# PowerSupply.net
KiCad netlist of a schematic drawn in Altium Designer
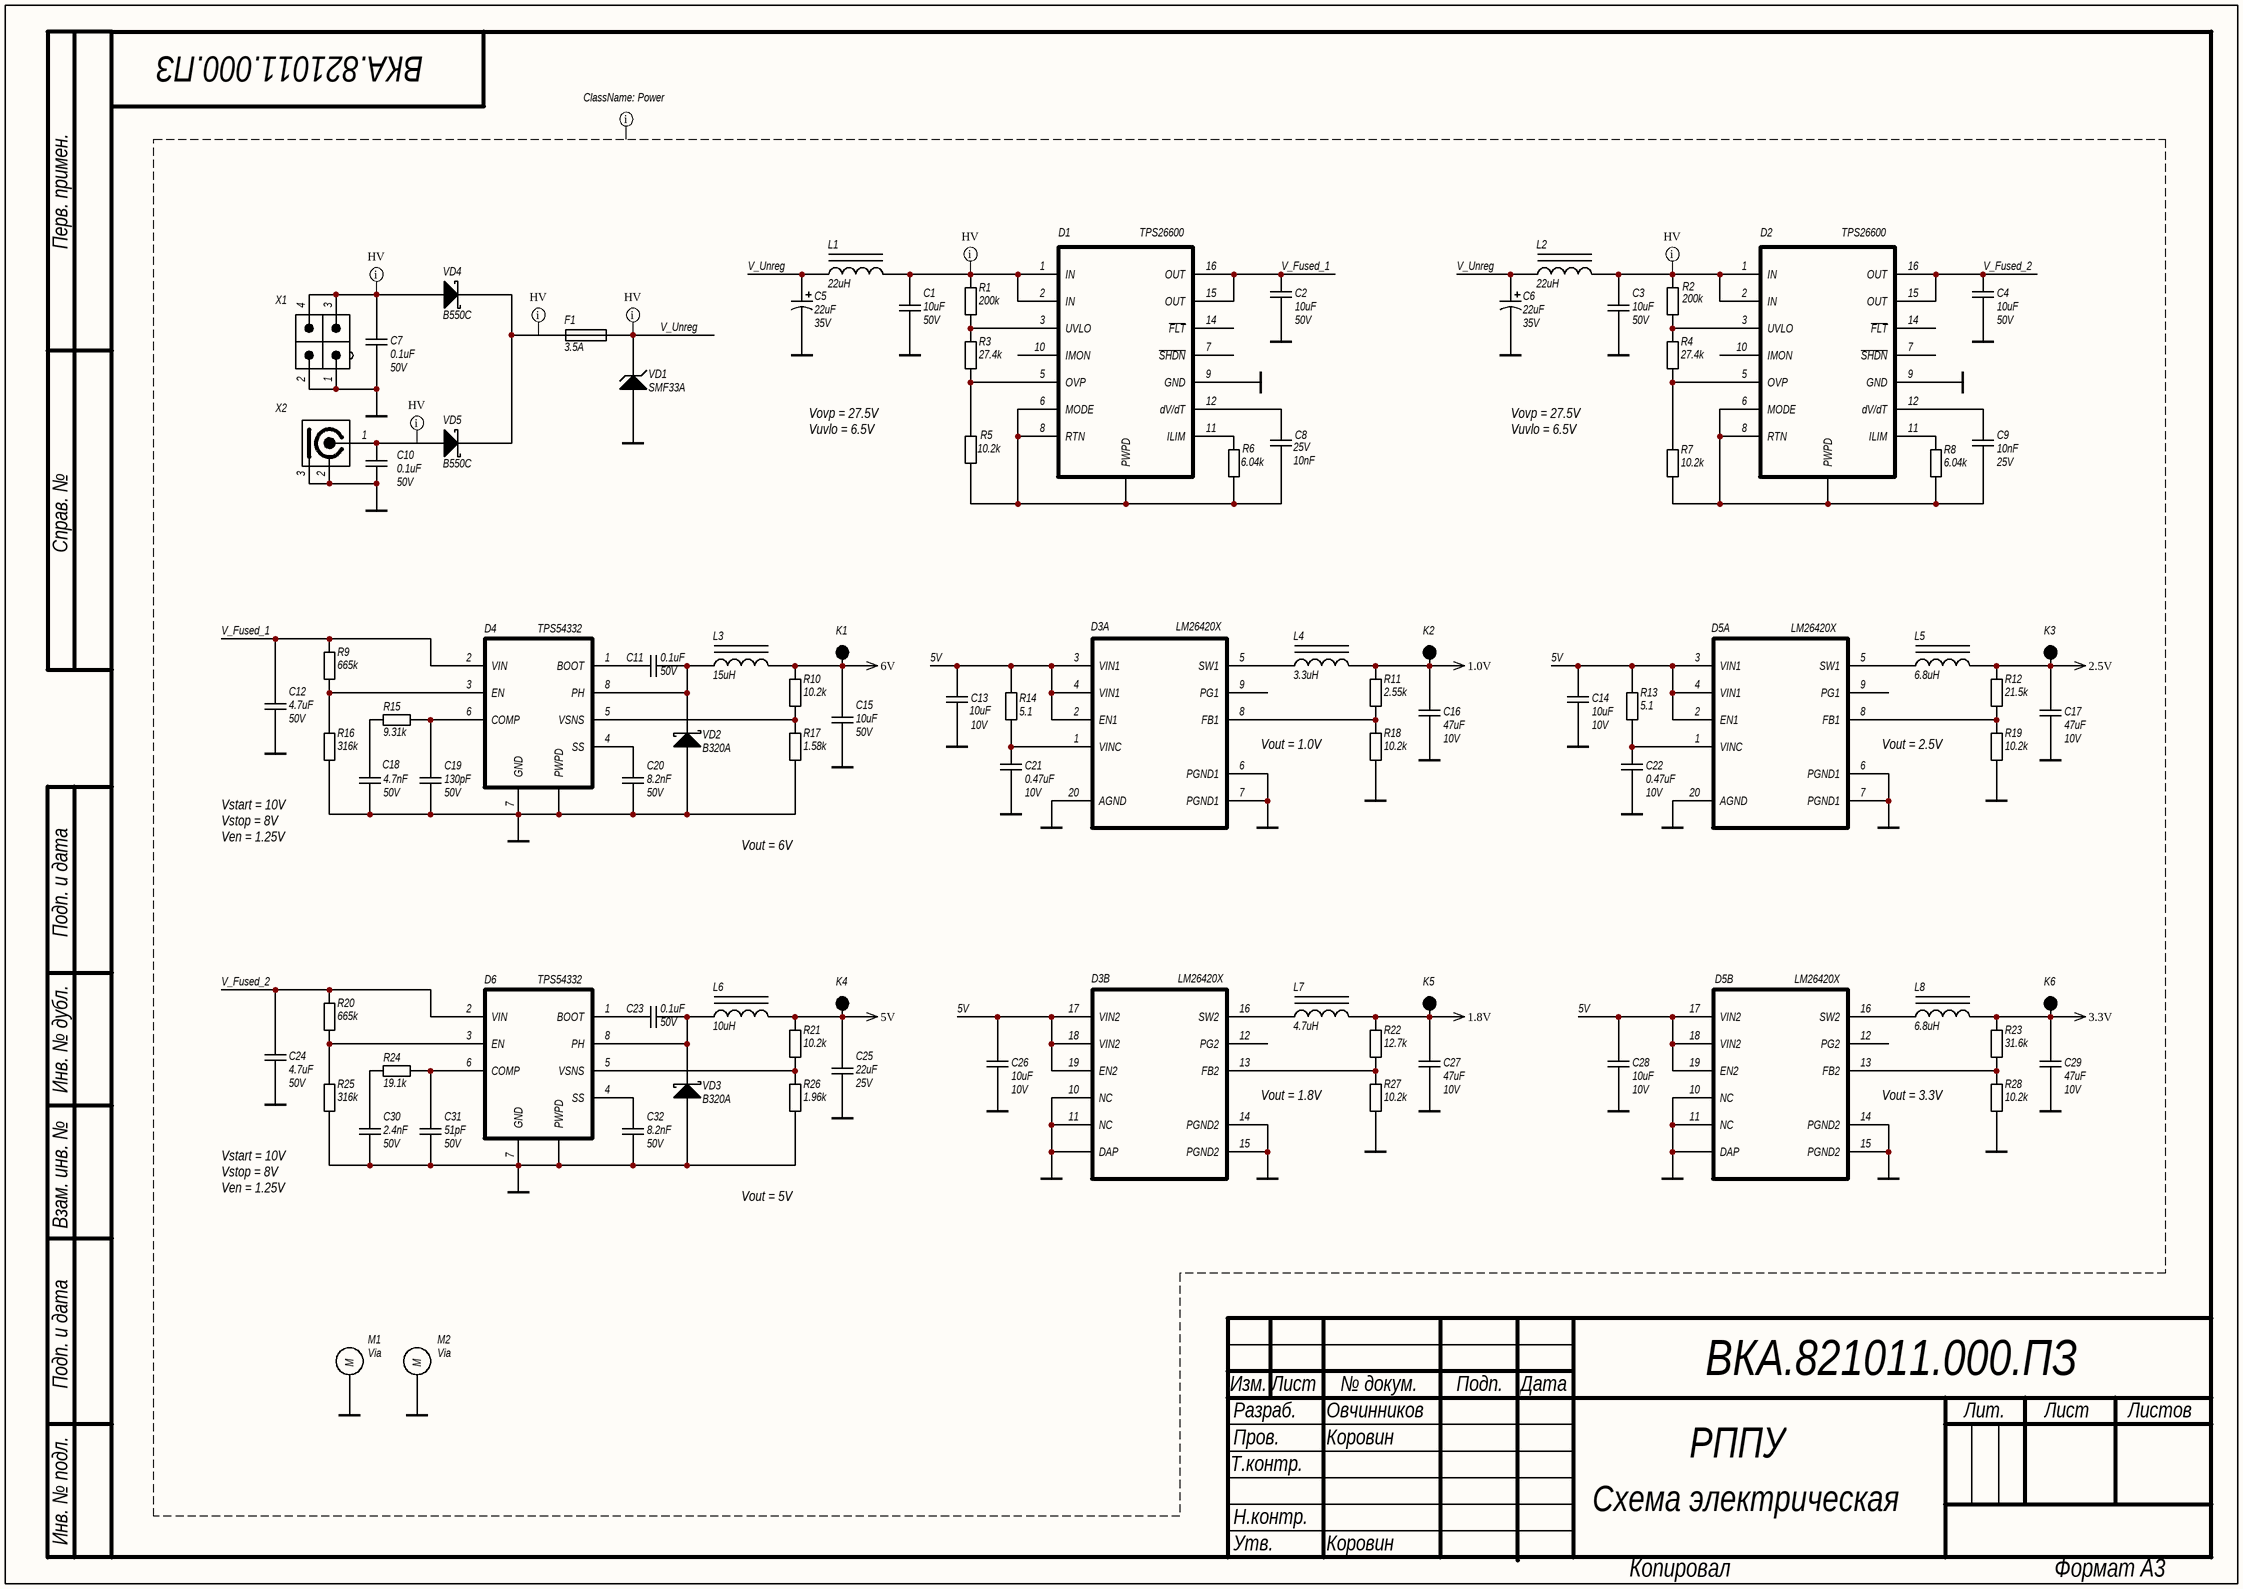
[diagram p0: PowerSupply.SchDoc]

(export (version "E")
  (design (tool "Eeschema 10.0.6"))
  (components
    (comp (ref "C1")
      (value "10uF")
      (footprint "C1210")
      (description "SMD Capacitor")
      (fields
        (field (name "MANUFACTURER") "Murata")
        (field (name "TOLERANCE") "10%")
        (field (name "VOLTAGE") "50V")
      )
      (libsource (lib "Kintex_SDR") (part "CAP uF"))
    )
    (comp (ref "C2")
      (value "10uF")
      (footprint "C1210")
      (description "SMD Capacitor")
      (fields
        (field (name "MANUFACTURER") "Murata")
        (field (name "TOLERANCE") "10%")
        (field (name "VOLTAGE") "50V")
      )
      (libsource (lib "Kintex_SDR") (part "CAP uF"))
    )
    (comp (ref "C3")
      (value "10uF")
      (footprint "C1210")
      (description "SMD Capacitor")
      (fields
        (field (name "MANUFACTURER") "Murata")
        (field (name "TOLERANCE") "10%")
        (field (name "VOLTAGE") "50V")
      )
      (libsource (lib "Kintex_SDR") (part "CAP uF"))
    )
    (comp (ref "C4")
      (value "10uF")
      (footprint "C1210")
      (description "SMD Capacitor")
      (fields
        (field (name "MANUFACTURER") "Murata")
        (field (name "TOLERANCE") "10%")
        (field (name "VOLTAGE") "50V")
      )
      (libsource (lib "Kintex_SDR") (part "CAP uF"))
    )
    (comp (ref "C5")
      (value "22uF")
      (footprint "Tantalum_D")
      (description "Tantalum Polarity SMD Capacitor")
      (fields
        (field (name "MANUFACTURER") "AVX Corporation")
        (field (name "TOLERANCE") "10%")
        (field (name "VOLTAGE") "35V")
      )
      (libsource (lib "Kintex_SDR") (part "Cap Polarity"))
    )
    (comp (ref "C6")
      (value "22uF")
      (footprint "Tantalum_D")
      (description "Tantalum Polarity SMD Capacitor")
      (fields
        (field (name "MANUFACTURER") "AVX Corporation")
        (field (name "TOLERANCE") "10%")
        (field (name "VOLTAGE") "35V")
      )
      (libsource (lib "Kintex_SDR") (part "Cap Polarity"))
    )
    (comp (ref "C7")
      (value "0.1uF")
      (footprint "C0402")
      (description "SMD Capacitor")
      (fields
        (field (name "MANUFACTURER") "Murata")
        (field (name "TOLERANCE") "10%")
        (field (name "VOLTAGE") "50V")
      )
      (libsource (lib "Kintex_SDR") (part "CAP"))
    )
    (comp (ref "C8")
      (value "10nF")
      (footprint "C0402")
      (description "SMD Capacitor")
      (fields
        (field (name "MANUFACTURER") "Murata")
        (field (name "TOLERANCE") "5%")
        (field (name "VOLTAGE") "25V")
      )
      (libsource (lib "Kintex_SDR") (part "CAP"))
    )
    (comp (ref "C9")
      (value "10nF")
      (footprint "C0402")
      (description "SMD Capacitor")
      (fields
        (field (name "MANUFACTURER") "Murata")
        (field (name "TOLERANCE") "5%")
        (field (name "VOLTAGE") "25V")
      )
      (libsource (lib "Kintex_SDR") (part "CAP"))
    )
    (comp (ref "C10")
      (value "0.1uF")
      (footprint "C0402")
      (description "SMD Capacitor")
      (fields
        (field (name "MANUFACTURER") "Murata")
        (field (name "TOLERANCE") "10%")
        (field (name "VOLTAGE") "50V")
      )
      (libsource (lib "Kintex_SDR") (part "CAP"))
    )
    (comp (ref "C11")
      (value "0.1uF")
      (footprint "C0402")
      (description "SMD Capacitor")
      (fields
        (field (name "MANUFACTURER") "Murata")
        (field (name "TOLERANCE") "10%")
        (field (name "VOLTAGE") "50V")
      )
      (libsource (lib "Kintex_SDR") (part "CAP"))
    )
    (comp (ref "C12")
      (value "4.7uF")
      (footprint "C0805")
      (description "SMD Capacitor")
      (fields
        (field (name "MANUFACTURER") "Murata")
        (field (name "TOLERANCE") "20%")
        (field (name "VOLTAGE") "50V")
      )
      (libsource (lib "Kintex_SDR") (part "CAP uF"))
    )
    (comp (ref "C13")
      (value "10uF")
      (footprint "C0805")
      (description "SMD Capacitor")
      (fields
        (field (name "MANUFACTURER") "Murata")
        (field (name "TOLERANCE") "10%")
        (field (name "VOLTAGE") "10V")
      )
      (libsource (lib "Kintex_SDR") (part "CAP uF"))
    )
    (comp (ref "C14")
      (value "10uF")
      (footprint "C0805")
      (description "SMD Capacitor")
      (fields
        (field (name "MANUFACTURER") "Murata")
        (field (name "TOLERANCE") "10%")
        (field (name "VOLTAGE") "10V")
      )
      (libsource (lib "Kintex_SDR") (part "CAP uF"))
    )
    (comp (ref "C15")
      (value "10uF")
      (footprint "C1210")
      (description "SMD Capacitor")
      (fields
        (field (name "MANUFACTURER") "Murata")
        (field (name "TOLERANCE") "10%")
        (field (name "VOLTAGE") "50V")
      )
      (libsource (lib "Kintex_SDR") (part "CAP uF"))
    )
    (comp (ref "C16")
      (value "47uF")
      (footprint "C1210")
      (description "SMD Capacitor")
      (fields
        (field (name "MANUFACTURER") "Murata")
        (field (name "TOLERANCE") "10%")
        (field (name "VOLTAGE") "10V")
      )
      (libsource (lib "Kintex_SDR") (part "CAP uF"))
    )
    (comp (ref "C17")
      (value "47uF")
      (footprint "C1210")
      (description "SMD Capacitor")
      (fields
        (field (name "MANUFACTURER") "Murata")
        (field (name "TOLERANCE") "10%")
        (field (name "VOLTAGE") "10V")
      )
      (libsource (lib "Kintex_SDR") (part "CAP uF"))
    )
    (comp (ref "C18")
      (value "4.7nF")
      (footprint "C0603")
      (description "SMD Capacitor")
      (fields
        (field (name "MANUFACTURER") "Murata")
        (field (name "TOLERANCE") "5%")
        (field (name "VOLTAGE") "50V")
      )
      (libsource (lib "Kintex_SDR") (part "CAP"))
    )
    (comp (ref "C19")
      (value "130pF")
      (footprint "C0402")
      (description "SMD Capacitor")
      (fields
        (field (name "MANUFACTURER") "Murata")
        (field (name "TOLERANCE") "5%")
        (field (name "VOLTAGE") "50V")
      )
      (libsource (lib "Kintex_SDR") (part "CAP"))
    )
    (comp (ref "C20")
      (value "8.2nF")
      (footprint "C0402")
      (description "SMD Capacitor")
      (fields
        (field (name "MANUFACTURER") "Murata")
        (field (name "TOLERANCE") "10%")
        (field (name "VOLTAGE") "50V")
      )
      (libsource (lib "Kintex_SDR") (part "CAP"))
    )
    (comp (ref "C21")
      (value "0.47uF")
      (footprint "C0603")
      (description "SMD Capacitor")
      (fields
        (field (name "MANUFACTURER") "Murata")
        (field (name "TOLERANCE") "10%")
        (field (name "VOLTAGE") "10V")
      )
      (libsource (lib "Kintex_SDR") (part "CAP"))
    )
    (comp (ref "C22")
      (value "0.47uF")
      (footprint "C0603")
      (description "SMD Capacitor")
      (fields
        (field (name "MANUFACTURER") "Murata")
        (field (name "TOLERANCE") "10%")
        (field (name "VOLTAGE") "10V")
      )
      (libsource (lib "Kintex_SDR") (part "CAP"))
    )
    (comp (ref "C23")
      (value "0.1uF")
      (footprint "C0402")
      (description "SMD Capacitor")
      (fields
        (field (name "MANUFACTURER") "Murata")
        (field (name "TOLERANCE") "10%")
        (field (name "VOLTAGE") "50V")
      )
      (libsource (lib "Kintex_SDR") (part "CAP"))
    )
    (comp (ref "C24")
      (value "4.7uF")
      (footprint "C0805")
      (description "SMD Capacitor")
      (fields
        (field (name "MANUFACTURER") "Murata")
        (field (name "TOLERANCE") "20%")
        (field (name "VOLTAGE") "50V")
      )
      (libsource (lib "Kintex_SDR") (part "CAP uF"))
    )
    (comp (ref "C25")
      (value "22uF")
      (footprint "C1210")
      (description "SMD Capacitor")
      (fields
        (field (name "MANUFACTURER") "Murata")
        (field (name "TOLERANCE") "10%")
        (field (name "VOLTAGE") "25V")
      )
      (libsource (lib "Kintex_SDR") (part "CAP uF"))
    )
    (comp (ref "C26")
      (value "10uF")
      (footprint "C0805")
      (description "SMD Capacitor")
      (fields
        (field (name "MANUFACTURER") "Murata")
        (field (name "TOLERANCE") "10%")
        (field (name "VOLTAGE") "10V")
      )
      (libsource (lib "Kintex_SDR") (part "CAP uF"))
    )
    (comp (ref "C27")
      (value "47uF")
      (footprint "C1210")
      (description "SMD Capacitor")
      (fields
        (field (name "MANUFACTURER") "Murata")
        (field (name "TOLERANCE") "10%")
        (field (name "VOLTAGE") "10V")
      )
      (libsource (lib "Kintex_SDR") (part "CAP uF"))
    )
    (comp (ref "C28")
      (value "10uF")
      (footprint "C0805")
      (description "SMD Capacitor")
      (fields
        (field (name "MANUFACTURER") "Murata")
        (field (name "TOLERANCE") "10%")
        (field (name "VOLTAGE") "10V")
      )
      (libsource (lib "Kintex_SDR") (part "CAP uF"))
    )
    (comp (ref "C29")
      (value "47uF")
      (footprint "C1210")
      (description "SMD Capacitor")
      (fields
        (field (name "MANUFACTURER") "Murata")
        (field (name "TOLERANCE") "10%")
        (field (name "VOLTAGE") "10V")
      )
      (libsource (lib "Kintex_SDR") (part "CAP uF"))
    )
    (comp (ref "C30")
      (value "2.4nF")
      (footprint "C0603")
      (description "SMD Capacitor")
      (fields
        (field (name "MANUFACTURER") "Murata")
        (field (name "TOLERANCE") "5%")
        (field (name "VOLTAGE") "50V")
      )
      (libsource (lib "Kintex_SDR") (part "CAP"))
    )
    (comp (ref "C31")
      (value "51pF")
      (footprint "C0402")
      (description "SMD Capacitor")
      (fields
        (field (name "MANUFACTURER") "Murata")
        (field (name "TOLERANCE") "5%")
        (field (name "VOLTAGE") "50V")
      )
      (libsource (lib "Kintex_SDR") (part "CAP"))
    )
    (comp (ref "C32")
      (value "8.2nF")
      (footprint "C0402")
      (description "SMD Capacitor")
      (fields
        (field (name "MANUFACTURER") "Murata")
        (field (name "TOLERANCE") "10%")
        (field (name "VOLTAGE") "50V")
      )
      (libsource (lib "Kintex_SDR") (part "CAP"))
    )
    (comp (ref "D1")
      (value "TPS26600")
      (footprint "R-PDSO-G16")
      (description "Industrial eFuse")
      (fields (field (name "VOLTAGE") "60V"))
      (libsource (lib "Kintex_SDR") (part "TPS26600"))
    )
    (comp (ref "D2")
      (value "TPS26600")
      (footprint "R-PDSO-G16")
      (description "Industrial eFuse")
      (fields (field (name "VOLTAGE") "60V"))
      (libsource (lib "Kintex_SDR") (part "TPS26600"))
    )
    (comp (ref "D3")
      (value "LM26420X")
      (footprint "HTSSOP-20")
      (description "Synchronous  DC-DC Converter")
      (libsource (lib "Kintex_SDR") (part "LM26420X"))
    )
    (comp (ref "D4")
      (value "TPS54332")
      (footprint "R-PDSO-G8")
      (description "Step-Down DC-DC Converter")
      (libsource (lib "Kintex_SDR") (part "TPS54332"))
    )
    (comp (ref "D5")
      (value "LM26420X")
      (footprint "HTSSOP-20")
      (description "Synchronous  DC-DC Converter")
      (libsource (lib "Kintex_SDR") (part "LM26420X"))
    )
    (comp (ref "D6")
      (value "TPS54332")
      (footprint "R-PDSO-G8")
      (description "Step-Down DC-DC Converter")
      (libsource (lib "Kintex_SDR") (part "TPS54332"))
    )
    (comp (ref "F1")
      (value "FUSE")
      (footprint "Fuse")
      (description "Chip SMD Fuse")
      (fields (field (name "VOLTAGE") "125V") (field (name "CURRENT") "3.5A"))
      (libsource (lib "Kintex_SDR") (part "FUSE"))
    )
    (comp (ref "K1")
      (value "6V")
      (footprint "Control Point")
      (libsource (lib "Kintex_SDR") (part "Test  Point"))
    )
    (comp (ref "K2")
      (value "1.0V")
      (footprint "Control Point")
      (libsource (lib "Kintex_SDR") (part "Test  Point"))
    )
    (comp (ref "K3")
      (value "2.5V")
      (footprint "Control Point")
      (libsource (lib "Kintex_SDR") (part "Test  Point"))
    )
    (comp (ref "K4")
      (value "5V")
      (footprint "Control Point")
      (libsource (lib "Kintex_SDR") (part "Test  Point"))
    )
    (comp (ref "K5")
      (value "1.8V")
      (footprint "Control Point")
      (libsource (lib "Kintex_SDR") (part "Test  Point"))
    )
    (comp (ref "K6")
      (value "3.3V")
      (footprint "Control Point")
      (libsource (lib "Kintex_SDR") (part "Test  Point"))
    )
    (comp (ref "L1")
      (value "22uH")
      (footprint "XAL6060-223")
      (description "Magnetic-Core Inductor")
      (fields (field (name "MANUFACTURER") "Coilcraft") (field (name "TOLERANCE") "±30%"))
      (libsource (lib "Kintex_SDR") (part "Inductor PWR"))
    )
    (comp (ref "L2")
      (value "22uH")
      (footprint "XAL6060-223")
      (description "Magnetic-Core Inductor")
      (fields (field (name "MANUFACTURER") "Coilcraft") (field (name "TOLERANCE") "±30%"))
      (libsource (lib "Kintex_SDR") (part "Inductor PWR"))
    )
    (comp (ref "L3")
      (value "15uH")
      (footprint "XAL5050")
      (description "Magnetic-Core Inductor")
      (fields (field (name "MANUFACTURER") "Coilcraft") (field (name "TOLERANCE") "±30%"))
      (libsource (lib "Kintex_SDR") (part "Inductor PWR"))
    )
    (comp (ref "L4")
      (value "3.3uH")
      (footprint "XAL4030")
      (description "Magnetic-Core Inductor")
      (fields (field (name "MANUFACTURER") "Coilcraft") (field (name "TOLERANCE") "±30%"))
      (libsource (lib "Kintex_SDR") (part "Inductor PWR"))
    )
    (comp (ref "L5")
      (value "6.8uH")
      (footprint "XAL4030")
      (description "Magnetic-Core Inductor")
      (fields (field (name "MANUFACTURER") "Coilcraft") (field (name "TOLERANCE") "±30%"))
      (libsource (lib "Kintex_SDR") (part "Inductor PWR"))
    )
    (comp (ref "L6")
      (value "10uH")
      (footprint "XAL5050")
      (description "Magnetic-Core Inductor")
      (fields (field (name "MANUFACTURER") "Coilcraft") (field (name "TOLERANCE") "±30%"))
      (libsource (lib "Kintex_SDR") (part "Inductor PWR"))
    )
    (comp (ref "L7")
      (value "4.7uH")
      (footprint "XAL4030")
      (description "Magnetic-Core Inductor")
      (fields (field (name "MANUFACTURER") "Coilcraft") (field (name "TOLERANCE") "±30%"))
      (libsource (lib "Kintex_SDR") (part "Inductor PWR"))
    )
    (comp (ref "L8")
      (value "6.8uH")
      (footprint "XAL4030")
      (description "Magnetic-Core Inductor")
      (fields (field (name "MANUFACTURER") "Coilcraft") (field (name "TOLERANCE") "±30%"))
      (libsource (lib "Kintex_SDR") (part "Inductor PWR"))
    )
    (comp (ref "M1")
      (value "Via")
      (footprint "Mechanical_Via")
      (description "Mechanical Via")
      (libsource (lib "Kintex_SDR") (part "Mechanical Via"))
    )
    (comp (ref "M2")
      (value "Via")
      (footprint "Mechanical_Via")
      (description "Mechanical Via")
      (libsource (lib "Kintex_SDR") (part "Mechanical Via"))
    )
    (comp (ref "R1")
      (value "200k")
      (footprint "R0402")
      (description "SMD Resistor")
      (fields (field (name "POWER") "0.062 Wt") (field (name "TOLERANCE") "1%"))
      (libsource (lib "Kintex_SDR") (part "RES"))
    )
    (comp (ref "R2")
      (value "200k")
      (footprint "R0402")
      (description "SMD Resistor")
      (fields (field (name "POWER") "0.062 Wt") (field (name "TOLERANCE") "1%"))
      (libsource (lib "") (part "RES_2"))
    )
    (comp (ref "R3")
      (value "27.4k")
      (footprint "R0402")
      (description "SMD Resistor")
      (fields (field (name "POWER") "0.062 Wt") (field (name "TOLERANCE") "1%"))
      (libsource (lib "Kintex_SDR") (part "RES"))
    )
    (comp (ref "R4")
      (value "27.4k")
      (footprint "R0402")
      (description "SMD Resistor")
      (fields (field (name "POWER") "0.062 Wt") (field (name "TOLERANCE") "1%"))
      (libsource (lib "Kintex_SDR") (part "RES"))
    )
    (comp (ref "R5")
      (value "10.2k")
      (footprint "R0402")
      (description "SMD Resistor")
      (fields (field (name "POWER") "0.062 Wt") (field (name "TOLERANCE") "1%"))
      (libsource (lib "") (part "RES_2"))
    )
    (comp (ref "R6")
      (value "6.04k")
      (footprint "R0402")
      (description "SMD Resistor")
      (fields (field (name "POWER") "0.062 Wt") (field (name "TOLERANCE") "1%"))
      (libsource (lib "Kintex_SDR") (part "RES"))
    )
    (comp (ref "R7")
      (value "10.2k")
      (footprint "R0402")
      (description "SMD Resistor")
      (fields (field (name "POWER") "0.062 Wt") (field (name "TOLERANCE") "1%"))
      (libsource (lib "Kintex_SDR") (part "RES"))
    )
    (comp (ref "R8")
      (value "6.04k")
      (footprint "R0402")
      (description "SMD Resistor")
      (fields (field (name "POWER") "0.062 Wt") (field (name "TOLERANCE") "1%"))
      (libsource (lib "Kintex_SDR") (part "RES"))
    )
    (comp (ref "R9")
      (value "665k")
      (footprint "R0402")
      (description "SMD Resistor")
      (fields (field (name "POWER") "0.062 Wt") (field (name "TOLERANCE") "1%"))
      (libsource (lib "Kintex_SDR") (part "RES"))
    )
    (comp (ref "R10")
      (value "10.2k")
      (footprint "R0402")
      (description "SMD Resistor")
      (fields (field (name "POWER") "0.062 Wt") (field (name "TOLERANCE") "1%"))
      (libsource (lib "Kintex_SDR") (part "RES"))
    )
    (comp (ref "R11")
      (value "2.55k")
      (footprint "R0402")
      (description "SMD Resistor")
      (fields (field (name "POWER") "0.062 Wt") (field (name "TOLERANCE") "1%"))
      (libsource (lib "Kintex_SDR") (part "RES"))
    )
    (comp (ref "R12")
      (value "21.5k")
      (footprint "R0402")
      (description "SMD Resistor")
      (fields (field (name "POWER") "0.062 Wt") (field (name "TOLERANCE") "1%"))
      (libsource (lib "Kintex_SDR") (part "RES"))
    )
    (comp (ref "R13")
      (value "5.1")
      (footprint "R0402")
      (description "SMD Resistor")
      (fields (field (name "POWER") "0.062 Wt") (field (name "TOLERANCE") "5%"))
      (libsource (lib "Kintex_SDR") (part "RES"))
    )
    (comp (ref "R14")
      (value "5.1")
      (footprint "R0402")
      (description "SMD Resistor")
      (fields (field (name "POWER") "0.062 Wt") (field (name "TOLERANCE") "5%"))
      (libsource (lib "") (part "RES_2"))
    )
    (comp (ref "R15")
      (value "9.31k")
      (footprint "R0402")
      (description "SMD Resistor")
      (fields (field (name "POWER") "0.062 Wt") (field (name "TOLERANCE") "1%"))
      (libsource (lib "") (part "RES_3"))
    )
    (comp (ref "R16")
      (value "316k")
      (footprint "R0402")
      (description "SMD Resistor")
      (fields (field (name "POWER") "0.062 Wt") (field (name "TOLERANCE") "1%"))
      (libsource (lib "Kintex_SDR") (part "RES"))
    )
    (comp (ref "R17")
      (value "1.58k")
      (footprint "R0402")
      (description "SMD Resistor")
      (fields (field (name "POWER") "0.062 Wt") (field (name "TOLERANCE") "1%"))
      (libsource (lib "Kintex_SDR") (part "RES"))
    )
    (comp (ref "R18")
      (value "10.2k")
      (footprint "R0402")
      (description "SMD Resistor")
      (fields (field (name "POWER") "0.062 Wt") (field (name "TOLERANCE") "1%"))
      (libsource (lib "Kintex_SDR") (part "RES"))
    )
    (comp (ref "R19")
      (value "10.2k")
      (footprint "R0402")
      (description "SMD Resistor")
      (fields (field (name "POWER") "0.062 Wt") (field (name "TOLERANCE") "1%"))
      (libsource (lib "Kintex_SDR") (part "RES"))
    )
    (comp (ref "R20")
      (value "665k")
      (footprint "R0402")
      (description "SMD Resistor")
      (fields (field (name "POWER") "0.062 Wt") (field (name "TOLERANCE") "1%"))
      (libsource (lib "Kintex_SDR") (part "RES"))
    )
    (comp (ref "R21")
      (value "10.2k")
      (footprint "R0402")
      (description "SMD Resistor")
      (fields (field (name "POWER") "0.062 Wt") (field (name "TOLERANCE") "1%"))
      (libsource (lib "Kintex_SDR") (part "RES"))
    )
    (comp (ref "R22")
      (value "12.7k")
      (footprint "R0402")
      (description "SMD Resistor")
      (fields (field (name "POWER") "0.062 Wt") (field (name "TOLERANCE") "1%"))
      (libsource (lib "Kintex_SDR") (part "RES"))
    )
    (comp (ref "R23")
      (value "31.6k")
      (footprint "R0402")
      (description "SMD Resistor")
      (fields (field (name "POWER") "0.062 Wt") (field (name "TOLERANCE") "1%"))
      (libsource (lib "Kintex_SDR") (part "RES"))
    )
    (comp (ref "R24")
      (value "19.1k")
      (footprint "R0402")
      (description "SMD Resistor")
      (fields (field (name "POWER") "0.062 Wt") (field (name "TOLERANCE") "1%"))
      (libsource (lib "") (part "RES_1"))
    )
    (comp (ref "R25")
      (value "316k")
      (footprint "R0402")
      (description "SMD Resistor")
      (fields (field (name "POWER") "0.062 Wt") (field (name "TOLERANCE") "1%"))
      (libsource (lib "Kintex_SDR") (part "RES"))
    )
    (comp (ref "R26")
      (value "1.96k")
      (footprint "R0402")
      (description "SMD Resistor")
      (fields (field (name "POWER") "0.062 Wt") (field (name "TOLERANCE") "1%"))
      (libsource (lib "Kintex_SDR") (part "RES"))
    )
    (comp (ref "R27")
      (value "10.2k")
      (footprint "R0402")
      (description "SMD Resistor")
      (fields (field (name "POWER") "0.062 Wt") (field (name "TOLERANCE") "1%"))
      (libsource (lib "Kintex_SDR") (part "RES"))
    )
    (comp (ref "R28")
      (value "10.2k")
      (footprint "R0402")
      (description "SMD Resistor")
      (fields (field (name "POWER") "0.062 Wt") (field (name "TOLERANCE") "1%"))
      (libsource (lib "Kintex_SDR") (part "RES"))
    )
    (comp (ref "VD1")
      (value "SMF33A")
      (footprint "SOD-123F")
      (description "TVS Diode")
      (fields (field (name "MANUFACTURER") "Littelfuse") (field (name "POWER") "200W"))
      (libsource (lib "Kintex_SDR") (part "TVS"))
    )
    (comp (ref "VD2")
      (value "B320A")
      (footprint "Diode_SMA")
      (description "Schottky Diode")
      (libsource (lib "Kintex_SDR") (part "Shottky"))
    )
    (comp (ref "VD3")
      (value "B320A")
      (footprint "Diode_SMA")
      (description "Schottky Diode")
      (libsource (lib "Kintex_SDR") (part "Shottky"))
    )
    (comp (ref "VD4")
      (value "B550C")
      (footprint "Diode_SMC")
      (description "Schottky Diode")
      (libsource (lib "Kintex_SDR") (part "Shottky"))
    )
    (comp (ref "VD5")
      (value "B550C")
      (footprint "Diode_SMC")
      (description "Schottky Diode")
      (libsource (lib "Kintex_SDR") (part "Shottky"))
    )
    (comp (ref "X1")
      (value "miniFit")
      (footprint "2x2 PWR_HDR")
      (description "2x2 miniFit DC Power Connector")
      (fields (field (name "VOLTAGE") "12V"))
      (libsource (lib "Kintex_SDR") (part "HDR 2x2 miniFit"))
    )
    (comp (ref "X2")
      (value "POWER")
      (footprint "DC_CONNECTOR")
      (description "DC Power Connector 6mm")
      (fields (field (name "VOLTAGE") "12V"))
      (libsource (lib "Kintex_SDR") (part "Connector DC"))
    )
  )
  (nets
    (net (code "1") (name "/V_Fused_1") (class "Default")
      (node (ref "C12") (pin "2") (pinfunction "2_2") (pintype "passive"))
      (node (ref "C2") (pin "2") (pinfunction "2_2") (pintype "passive"))
      (node (ref "D1") (pin "15") (pinfunction "OUT_15") (pintype "passive"))
      (node (ref "D1") (pin "16") (pinfunction "OUT_16") (pintype "passive"))
      (node (ref "D4") (pin "2") (pinfunction "VIN_2") (pintype "passive"))
      (node (ref "R9") (pin "2") (pinfunction "2_2") (pintype "passive"))
    )
    (net (code "2") (name "/V_Fused_2") (class "Default")
      (node (ref "C24") (pin "2") (pinfunction "2_2") (pintype "passive"))
      (node (ref "C4") (pin "2") (pinfunction "2_2") (pintype "passive"))
      (node (ref "D2") (pin "15") (pinfunction "OUT_15") (pintype "passive"))
      (node (ref "D2") (pin "16") (pinfunction "OUT_16") (pintype "passive"))
      (node (ref "D6") (pin "2") (pinfunction "VIN_2") (pintype "passive"))
      (node (ref "R20") (pin "2") (pinfunction "2_2") (pintype "passive"))
    )
    (net (code "3") (name "/V_Unreg") (class "Default")
      (node (ref "C5") (pin "1") (pinfunction "1_1") (pintype "passive"))
      (node (ref "C6") (pin "1") (pinfunction "1_1") (pintype "passive"))
      (node (ref "F1") (pin "2") (pinfunction "2_2") (pintype "passive"))
      (node (ref "L1") (pin "1") (pinfunction "1_1") (pintype "passive"))
      (node (ref "L2") (pin "1") (pinfunction "1_1") (pintype "passive"))
      (node (ref "VD1") (pin "1") (pinfunction "K_1") (pintype "passive"))
    )
    (net (code "4") (name "1.0V") (class "Default")
      (node (ref "C16") (pin "2") (pinfunction "2_2") (pintype "passive"))
      (node (ref "K2") (pin "1") (pinfunction "1_1") (pintype "passive"))
      (node (ref "L4") (pin "2") (pinfunction "2_2") (pintype "passive"))
      (node (ref "R11") (pin "2") (pinfunction "2_2") (pintype "passive"))
    )
    (net (code "5") (name "1.8V") (class "Default")
      (node (ref "C27") (pin "2") (pinfunction "2_2") (pintype "passive"))
      (node (ref "K5") (pin "1") (pinfunction "1_1") (pintype "passive"))
      (node (ref "L7") (pin "2") (pinfunction "2_2") (pintype "passive"))
      (node (ref "R22") (pin "2") (pinfunction "2_2") (pintype "passive"))
    )
    (net (code "6") (name "2.5V") (class "Default")
      (node (ref "C17") (pin "2") (pinfunction "2_2") (pintype "passive"))
      (node (ref "K3") (pin "1") (pinfunction "1_1") (pintype "passive"))
      (node (ref "L5") (pin "2") (pinfunction "2_2") (pintype "passive"))
      (node (ref "R12") (pin "2") (pinfunction "2_2") (pintype "passive"))
    )
    (net (code "7") (name "3.3V") (class "Default")
      (node (ref "C29") (pin "2") (pinfunction "2_2") (pintype "passive"))
      (node (ref "K6") (pin "1") (pinfunction "1_1") (pintype "passive"))
      (node (ref "L8") (pin "2") (pinfunction "2_2") (pintype "passive"))
      (node (ref "R23") (pin "2") (pinfunction "2_2") (pintype "passive"))
    )
    (net (code "8") (name "5V") (class "Default")
      (node (ref "C13") (pin "2") (pinfunction "2_2") (pintype "passive"))
      (node (ref "C14") (pin "2") (pinfunction "2_2") (pintype "passive"))
      (node (ref "C25") (pin "2") (pinfunction "2_2") (pintype "passive"))
      (node (ref "C26") (pin "2") (pinfunction "2_2") (pintype "passive"))
      (node (ref "C28") (pin "2") (pinfunction "2_2") (pintype "passive"))
      (node (ref "D3") (pin "17") (pinfunction "VIN2_17") (pintype "passive"))
      (node (ref "D3") (pin "18") (pinfunction "VIN2_18") (pintype "passive"))
      (node (ref "D3") (pin "19") (pinfunction "EN2_19") (pintype "passive"))
      (node (ref "D3") (pin "2") (pinfunction "EN1_2") (pintype "passive"))
      (node (ref "D3") (pin "3") (pinfunction "VIN1_3") (pintype "passive"))
      (node (ref "D3") (pin "4") (pinfunction "VIN1_4") (pintype "passive"))
      (node (ref "D5") (pin "17") (pinfunction "VIN2_17") (pintype "passive"))
      (node (ref "D5") (pin "18") (pinfunction "VIN2_18") (pintype "passive"))
      (node (ref "D5") (pin "19") (pinfunction "EN2_19") (pintype "passive"))
      (node (ref "D5") (pin "2") (pinfunction "EN1_2") (pintype "passive"))
      (node (ref "D5") (pin "3") (pinfunction "VIN1_3") (pintype "passive"))
      (node (ref "D5") (pin "4") (pinfunction "VIN1_4") (pintype "passive"))
      (node (ref "K4") (pin "1") (pinfunction "1_1") (pintype "passive"))
      (node (ref "L6") (pin "2") (pinfunction "2_2") (pintype "passive"))
      (node (ref "R13") (pin "2") (pinfunction "2_2") (pintype "passive"))
      (node (ref "R14") (pin "1") (pinfunction "1_1") (pintype "passive"))
      (node (ref "R21") (pin "2") (pinfunction "2_2") (pintype "passive"))
    )
    (net (code "9") (name "6V") (class "Default")
      (node (ref "C15") (pin "2") (pinfunction "2_2") (pintype "passive"))
      (node (ref "K1") (pin "1") (pinfunction "1_1") (pintype "passive"))
      (node (ref "L3") (pin "2") (pinfunction "2_2") (pintype "passive"))
      (node (ref "R10") (pin "2") (pinfunction "2_2") (pintype "passive"))
    )
    (net (code "10") (name "GND") (class "Default")
      (node (ref "C1") (pin "1") (pinfunction "1_1") (pintype "passive"))
      (node (ref "C10") (pin "1") (pinfunction "1_1") (pintype "passive"))
      (node (ref "C12") (pin "1") (pinfunction "1_1") (pintype "passive"))
      (node (ref "C13") (pin "1") (pinfunction "1_1") (pintype "passive"))
      (node (ref "C14") (pin "1") (pinfunction "1_1") (pintype "passive"))
      (node (ref "C15") (pin "1") (pinfunction "1_1") (pintype "passive"))
      (node (ref "C16") (pin "1") (pinfunction "1_1") (pintype "passive"))
      (node (ref "C17") (pin "1") (pinfunction "1_1") (pintype "passive"))
      (node (ref "C18") (pin "2") (pinfunction "2_2") (pintype "passive"))
      (node (ref "C19") (pin "1") (pinfunction "1_1") (pintype "passive"))
      (node (ref "C2") (pin "1") (pinfunction "1_1") (pintype "passive"))
      (node (ref "C20") (pin "1") (pinfunction "1_1") (pintype "passive"))
      (node (ref "C21") (pin "2") (pinfunction "2_2") (pintype "passive"))
      (node (ref "C22") (pin "1") (pinfunction "1_1") (pintype "passive"))
      (node (ref "C24") (pin "1") (pinfunction "1_1") (pintype "passive"))
      (node (ref "C25") (pin "1") (pinfunction "1_1") (pintype "passive"))
      (node (ref "C26") (pin "1") (pinfunction "1_1") (pintype "passive"))
      (node (ref "C27") (pin "1") (pinfunction "1_1") (pintype "passive"))
      (node (ref "C28") (pin "1") (pinfunction "1_1") (pintype "passive"))
      (node (ref "C29") (pin "1") (pinfunction "1_1") (pintype "passive"))
      (node (ref "C3") (pin "1") (pinfunction "1_1") (pintype "passive"))
      (node (ref "C30") (pin "1") (pinfunction "1_1") (pintype "passive"))
      (node (ref "C31") (pin "1") (pinfunction "1_1") (pintype "passive"))
      (node (ref "C32") (pin "1") (pinfunction "1_1") (pintype "passive"))
      (node (ref "C4") (pin "1") (pinfunction "1_1") (pintype "passive"))
      (node (ref "C5") (pin "2") (pinfunction "2_2") (pintype "passive"))
      (node (ref "C6") (pin "2") (pinfunction "2_2") (pintype "passive"))
      (node (ref "C7") (pin "1") (pinfunction "1_1") (pintype "passive"))
      (node (ref "D1") (pin "9") (pinfunction "GND_9") (pintype "passive"))
      (node (ref "D2") (pin "9") (pinfunction "GND_9") (pintype "passive"))
      (node (ref "D3") (pin "10") (pinfunction "NC_10") (pintype "passive"))
      (node (ref "D3") (pin "11") (pinfunction "NC_11") (pintype "passive"))
      (node (ref "D3") (pin "14") (pinfunction "PGND2_14") (pintype "passive"))
      (node (ref "D3") (pin "15") (pinfunction "PGND2_15") (pintype "passive"))
      (node (ref "D3") (pin "20") (pinfunction "AGND_20") (pintype "passive"))
      (node (ref "D3") (pin "21") (pinfunction "DAP_21") (pintype "passive"))
      (node (ref "D3") (pin "6") (pinfunction "PGND1_6") (pintype "passive"))
      (node (ref "D3") (pin "7") (pinfunction "PGND1_7") (pintype "passive"))
      (node (ref "D4") (pin "7") (pinfunction "GND_7") (pintype "passive"))
      (node (ref "D4") (pin "9") (pinfunction "PWPD_9") (pintype "passive"))
      (node (ref "D5") (pin "10") (pinfunction "NC_10") (pintype "passive"))
      (node (ref "D5") (pin "11") (pinfunction "NC_11") (pintype "passive"))
      (node (ref "D5") (pin "14") (pinfunction "PGND2_14") (pintype "passive"))
      (node (ref "D5") (pin "15") (pinfunction "PGND2_15") (pintype "passive"))
      (node (ref "D5") (pin "20") (pinfunction "AGND_20") (pintype "passive"))
      (node (ref "D5") (pin "21") (pinfunction "DAP_21") (pintype "passive"))
      (node (ref "D5") (pin "6") (pinfunction "PGND1_6") (pintype "passive"))
      (node (ref "D5") (pin "7") (pinfunction "PGND1_7") (pintype "passive"))
      (node (ref "D6") (pin "7") (pinfunction "GND_7") (pintype "passive"))
      (node (ref "D6") (pin "9") (pinfunction "PWPD_9") (pintype "passive"))
      (node (ref "M1") (pin "0") (pinfunction "M_0") (pintype "passive"))
      (node (ref "M2") (pin "0") (pinfunction "M_0") (pintype "passive"))
      (node (ref "R16") (pin "1") (pinfunction "1_1") (pintype "passive"))
      (node (ref "R17") (pin "1") (pinfunction "1_1") (pintype "passive"))
      (node (ref "R18") (pin "1") (pinfunction "1_1") (pintype "passive"))
      (node (ref "R19") (pin "1") (pinfunction "1_1") (pintype "passive"))
      (node (ref "R25") (pin "1") (pinfunction "1_1") (pintype "passive"))
      (node (ref "R26") (pin "1") (pinfunction "1_1") (pintype "passive"))
      (node (ref "R27") (pin "1") (pinfunction "1_1") (pintype "passive"))
      (node (ref "R28") (pin "1") (pinfunction "1_1") (pintype "passive"))
      (node (ref "VD1") (pin "2") (pinfunction "A_2") (pintype "passive"))
      (node (ref "VD2") (pin "2") (pinfunction "A_2") (pintype "passive"))
      (node (ref "VD3") (pin "2") (pinfunction "A_2") (pintype "passive"))
      (node (ref "X1") (pin "1") (pinfunction "1_1") (pintype "passive"))
      (node (ref "X1") (pin "2") (pinfunction "2_2") (pintype "passive"))
      (node (ref "X2") (pin "2") (pinfunction "GND_2") (pintype "power_in"))
      (node (ref "X2") (pin "3") (pinfunction "GND_3") (pintype "passive"))
    )
    (net (code "11") (name "Net-(C1-Pad2)") (class "Default")
      (node (ref "C1") (pin "2") (pinfunction "2_2") (pintype "passive"))
      (node (ref "D1") (pin "1") (pinfunction "IN_1") (pintype "passive"))
      (node (ref "D1") (pin "2") (pinfunction "IN_2") (pintype "passive"))
      (node (ref "L1") (pin "2") (pinfunction "2_2") (pintype "passive"))
      (node (ref "R1") (pin "2") (pinfunction "2_2") (pintype "passive"))
    )
    (net (code "12") (name "Net-(C3-Pad2)") (class "Default")
      (node (ref "C3") (pin "2") (pinfunction "2_2") (pintype "passive"))
      (node (ref "D2") (pin "1") (pinfunction "IN_1") (pintype "passive"))
      (node (ref "D2") (pin "2") (pinfunction "IN_2") (pintype "passive"))
      (node (ref "L2") (pin "2") (pinfunction "2_2") (pintype "passive"))
      (node (ref "R2") (pin "1") (pinfunction "1_1") (pintype "passive"))
    )
    (net (code "13") (name "Net-(C18-Pad1)") (class "Default")
      (node (ref "C18") (pin "1") (pinfunction "1_1") (pintype "passive"))
      (node (ref "R15") (pin "1") (pinfunction "1_1") (pintype "passive"))
    )
    (net (code "14") (name "Net-(C30-Pad2)") (class "Default")
      (node (ref "C30") (pin "2") (pinfunction "2_2") (pintype "passive"))
      (node (ref "R24") (pin "2") (pinfunction "2_2") (pintype "passive"))
    )
    (net (code "15") (name "Net-(D1-ILIM)") (class "Default")
      (node (ref "D1") (pin "11") (pinfunction "ILIM_11") (pintype "passive"))
      (node (ref "R6") (pin "2") (pinfunction "2_2") (pintype "passive"))
    )
    (net (code "16") (name "Net-(D1-MODE)") (class "Default")
      (node (ref "C8") (pin "1") (pinfunction "1_1") (pintype "passive"))
      (node (ref "D1") (pin "17") (pinfunction "PWPD_17") (pintype "passive"))
      (node (ref "D1") (pin "6") (pinfunction "MODE_6") (pintype "passive"))
      (node (ref "D1") (pin "8") (pinfunction "RTN_8") (pintype "passive"))
      (node (ref "R5") (pin "2") (pinfunction "2_2") (pintype "passive"))
      (node (ref "R6") (pin "1") (pinfunction "1_1") (pintype "passive"))
    )
    (net (code "17") (name "Net-(D1-OVP)") (class "Default")
      (node (ref "D1") (pin "5") (pinfunction "OVP_5") (pintype "passive"))
      (node (ref "R3") (pin "1") (pinfunction "1_1") (pintype "passive"))
      (node (ref "R5") (pin "1") (pinfunction "1_1") (pintype "passive"))
    )
    (net (code "18") (name "Net-(D1-UVLO)") (class "Default")
      (node (ref "D1") (pin "3") (pinfunction "UVLO_3") (pintype "passive"))
      (node (ref "R1") (pin "1") (pinfunction "1_1") (pintype "passive"))
      (node (ref "R3") (pin "2") (pinfunction "2_2") (pintype "passive"))
    )
    (net (code "19") (name "Net-(D1-dV{slash}dT)") (class "Default")
      (node (ref "C8") (pin "2") (pinfunction "2_2") (pintype "passive"))
      (node (ref "D1") (pin "12") (pinfunction "dV/dT_12") (pintype "passive"))
    )
    (net (code "20") (name "Net-(D2-ILIM)") (class "Default")
      (node (ref "D2") (pin "11") (pinfunction "ILIM_11") (pintype "passive"))
      (node (ref "R8") (pin "2") (pinfunction "2_2") (pintype "passive"))
    )
    (net (code "21") (name "Net-(D2-MODE)") (class "Default")
      (node (ref "C9") (pin "1") (pinfunction "1_1") (pintype "passive"))
      (node (ref "D2") (pin "17") (pinfunction "PWPD_17") (pintype "passive"))
      (node (ref "D2") (pin "6") (pinfunction "MODE_6") (pintype "passive"))
      (node (ref "D2") (pin "8") (pinfunction "RTN_8") (pintype "passive"))
      (node (ref "R7") (pin "1") (pinfunction "1_1") (pintype "passive"))
      (node (ref "R8") (pin "1") (pinfunction "1_1") (pintype "passive"))
    )
    (net (code "22") (name "Net-(D2-OVP)") (class "Default")
      (node (ref "D2") (pin "5") (pinfunction "OVP_5") (pintype "passive"))
      (node (ref "R4") (pin "1") (pinfunction "1_1") (pintype "passive"))
      (node (ref "R7") (pin "2") (pinfunction "2_2") (pintype "passive"))
    )
    (net (code "23") (name "Net-(D2-UVLO)") (class "Default")
      (node (ref "D2") (pin "3") (pinfunction "UVLO_3") (pintype "passive"))
      (node (ref "R2") (pin "2") (pinfunction "2_2") (pintype "passive"))
      (node (ref "R4") (pin "2") (pinfunction "2_2") (pintype "passive"))
    )
    (net (code "24") (name "Net-(D2-dV{slash}dT)") (class "Default")
      (node (ref "C9") (pin "2") (pinfunction "2_2") (pintype "passive"))
      (node (ref "D2") (pin "12") (pinfunction "dV/dT_12") (pintype "passive"))
    )
    (net (code "25") (name "Net-(D3A-FB1)") (class "Default")
      (node (ref "D3") (pin "8") (pinfunction "FB1_8") (pintype "passive"))
      (node (ref "R11") (pin "1") (pinfunction "1_1") (pintype "passive"))
      (node (ref "R18") (pin "2") (pinfunction "2_2") (pintype "passive"))
    )
    (net (code "26") (name "Net-(D3A-SW1)") (class "Default")
      (node (ref "D3") (pin "5") (pinfunction "SW1_5") (pintype "passive"))
      (node (ref "L4") (pin "1") (pinfunction "1_1") (pintype "passive"))
    )
    (net (code "27") (name "Net-(D3A-VINC)") (class "Default")
      (node (ref "C21") (pin "1") (pinfunction "1_1") (pintype "passive"))
      (node (ref "D3") (pin "1") (pinfunction "VINC_1") (pintype "passive"))
      (node (ref "R14") (pin "2") (pinfunction "2_2") (pintype "passive"))
    )
    (net (code "28") (name "Net-(D3B-FB2)") (class "Default")
      (node (ref "D3") (pin "13") (pinfunction "FB2_13") (pintype "passive"))
      (node (ref "R22") (pin "1") (pinfunction "1_1") (pintype "passive"))
      (node (ref "R27") (pin "2") (pinfunction "2_2") (pintype "passive"))
    )
    (net (code "29") (name "Net-(D3B-SW2)") (class "Default")
      (node (ref "D3") (pin "16") (pinfunction "SW2_16") (pintype "passive"))
      (node (ref "L7") (pin "1") (pinfunction "1_1") (pintype "passive"))
    )
    (net (code "30") (name "Net-(D4-BOOT)") (class "Default")
      (node (ref "C11") (pin "2") (pinfunction "2_2") (pintype "passive"))
      (node (ref "D4") (pin "1") (pinfunction "BOOT_1") (pintype "passive"))
    )
    (net (code "31") (name "Net-(D4-COMP)") (class "Default")
      (node (ref "C19") (pin "2") (pinfunction "2_2") (pintype "passive"))
      (node (ref "D4") (pin "6") (pinfunction "COMP_6") (pintype "passive"))
      (node (ref "R15") (pin "2") (pinfunction "2_2") (pintype "passive"))
    )
    (net (code "32") (name "Net-(D4-EN)") (class "Default")
      (node (ref "D4") (pin "3") (pinfunction "EN_3") (pintype "passive"))
      (node (ref "R16") (pin "2") (pinfunction "2_2") (pintype "passive"))
      (node (ref "R9") (pin "1") (pinfunction "1_1") (pintype "passive"))
    )
    (net (code "33") (name "Net-(D4-PH)") (class "Default")
      (node (ref "C11") (pin "1") (pinfunction "1_1") (pintype "passive"))
      (node (ref "D4") (pin "8") (pinfunction "PH_8") (pintype "passive"))
      (node (ref "L3") (pin "1") (pinfunction "1_1") (pintype "passive"))
      (node (ref "VD2") (pin "1") (pinfunction "K_1") (pintype "passive"))
    )
    (net (code "34") (name "Net-(D4-SS)") (class "Default")
      (node (ref "C20") (pin "2") (pinfunction "2_2") (pintype "passive"))
      (node (ref "D4") (pin "4") (pinfunction "SS_4") (pintype "passive"))
    )
    (net (code "35") (name "Net-(D4-VSNS)") (class "Default")
      (node (ref "D4") (pin "5") (pinfunction "VSNS_5") (pintype "passive"))
      (node (ref "R10") (pin "1") (pinfunction "1_1") (pintype "passive"))
      (node (ref "R17") (pin "2") (pinfunction "2_2") (pintype "passive"))
    )
    (net (code "36") (name "Net-(D5A-FB1)") (class "Default")
      (node (ref "D5") (pin "8") (pinfunction "FB1_8") (pintype "passive"))
      (node (ref "R12") (pin "1") (pinfunction "1_1") (pintype "passive"))
      (node (ref "R19") (pin "2") (pinfunction "2_2") (pintype "passive"))
    )
    (net (code "37") (name "Net-(D5A-SW1)") (class "Default")
      (node (ref "D5") (pin "5") (pinfunction "SW1_5") (pintype "passive"))
      (node (ref "L5") (pin "1") (pinfunction "1_1") (pintype "passive"))
    )
    (net (code "38") (name "Net-(D5A-VINC)") (class "Default")
      (node (ref "C22") (pin "2") (pinfunction "2_2") (pintype "passive"))
      (node (ref "D5") (pin "1") (pinfunction "VINC_1") (pintype "passive"))
      (node (ref "R13") (pin "1") (pinfunction "1_1") (pintype "passive"))
    )
    (net (code "39") (name "Net-(D5B-FB2)") (class "Default")
      (node (ref "D5") (pin "13") (pinfunction "FB2_13") (pintype "passive"))
      (node (ref "R23") (pin "1") (pinfunction "1_1") (pintype "passive"))
      (node (ref "R28") (pin "2") (pinfunction "2_2") (pintype "passive"))
    )
    (net (code "40") (name "Net-(D5B-SW2)") (class "Default")
      (node (ref "D5") (pin "16") (pinfunction "SW2_16") (pintype "passive"))
      (node (ref "L8") (pin "1") (pinfunction "1_1") (pintype "passive"))
    )
    (net (code "41") (name "Net-(D6-BOOT)") (class "Default")
      (node (ref "C23") (pin "2") (pinfunction "2_2") (pintype "passive"))
      (node (ref "D6") (pin "1") (pinfunction "BOOT_1") (pintype "passive"))
    )
    (net (code "42") (name "Net-(D6-COMP)") (class "Default")
      (node (ref "C31") (pin "2") (pinfunction "2_2") (pintype "passive"))
      (node (ref "D6") (pin "6") (pinfunction "COMP_6") (pintype "passive"))
      (node (ref "R24") (pin "1") (pinfunction "1_1") (pintype "passive"))
    )
    (net (code "43") (name "Net-(D6-EN)") (class "Default")
      (node (ref "D6") (pin "3") (pinfunction "EN_3") (pintype "passive"))
      (node (ref "R20") (pin "1") (pinfunction "1_1") (pintype "passive"))
      (node (ref "R25") (pin "2") (pinfunction "2_2") (pintype "passive"))
    )
    (net (code "44") (name "Net-(D6-PH)") (class "Default")
      (node (ref "C23") (pin "1") (pinfunction "1_1") (pintype "passive"))
      (node (ref "D6") (pin "8") (pinfunction "PH_8") (pintype "passive"))
      (node (ref "L6") (pin "1") (pinfunction "1_1") (pintype "passive"))
      (node (ref "VD3") (pin "1") (pinfunction "K_1") (pintype "passive"))
    )
    (net (code "45") (name "Net-(D6-SS)") (class "Default")
      (node (ref "C32") (pin "2") (pinfunction "2_2") (pintype "passive"))
      (node (ref "D6") (pin "4") (pinfunction "SS_4") (pintype "passive"))
    )
    (net (code "46") (name "Net-(D6-VSNS)") (class "Default")
      (node (ref "D6") (pin "5") (pinfunction "VSNS_5") (pintype "passive"))
      (node (ref "R21") (pin "1") (pinfunction "1_1") (pintype "passive"))
      (node (ref "R26") (pin "2") (pinfunction "2_2") (pintype "passive"))
    )
    (net (code "47") (name "Net-(VD4-A)") (class "Default")
      (node (ref "C7") (pin "2") (pinfunction "2_2") (pintype "passive"))
      (node (ref "VD4") (pin "2") (pinfunction "A_2") (pintype "passive"))
      (node (ref "X1") (pin "3") (pinfunction "3_3") (pintype "passive"))
      (node (ref "X1") (pin "4") (pinfunction "4_4") (pintype "passive"))
    )
    (net (code "48") (name "Net-(VD4-K)") (class "Default")
      (node (ref "F1") (pin "1") (pinfunction "1_1") (pintype "passive"))
      (node (ref "VD4") (pin "1") (pinfunction "K_1") (pintype "passive"))
      (node (ref "VD5") (pin "1") (pinfunction "K_1") (pintype "passive"))
    )
    (net (code "49") (name "Net-(VD5-A)") (class "Default")
      (node (ref "C10") (pin "2") (pinfunction "2_2") (pintype "passive"))
      (node (ref "VD5") (pin "2") (pinfunction "A_2") (pintype "passive"))
      (node (ref "X2") (pin "1") (pinfunction "RF_1") (pintype "passive"))
    )
    (net (code "50") (name "unconnected-(D1-IMON-Pad10)") (class "Default")
      (node (ref "D1") (pin "10") (pinfunction "IMON_10") (pintype "passive"))
    )
    (net (code "51") (name "unconnected-(D1-~{FLT}-Pad14)") (class "Default")
      (node (ref "D1") (pin "14") (pinfunction "~{FLT}_14") (pintype "passive"))
    )
    (net (code "52") (name "unconnected-(D1-~{SHDN}-Pad7)") (class "Default")
      (node (ref "D1") (pin "7") (pinfunction "~{SHDN}_7") (pintype "passive"))
    )
    (net (code "53") (name "unconnected-(D2-IMON-Pad10)") (class "Default")
      (node (ref "D2") (pin "10") (pinfunction "IMON_10") (pintype "passive"))
    )
    (net (code "54") (name "unconnected-(D2-~{FLT}-Pad14)") (class "Default")
      (node (ref "D2") (pin "14") (pinfunction "~{FLT}_14") (pintype "passive"))
    )
    (net (code "55") (name "unconnected-(D2-~{SHDN}-Pad7)") (class "Default")
      (node (ref "D2") (pin "7") (pinfunction "~{SHDN}_7") (pintype "passive"))
    )
    (net (code "56") (name "unconnected-(D3A-PG1-Pad9)") (class "Default")
      (node (ref "D3") (pin "9") (pinfunction "PG1_9") (pintype "passive"))
    )
    (net (code "57") (name "unconnected-(D3B-PG2-Pad12)") (class "Default")
      (node (ref "D3") (pin "12") (pinfunction "PG2_12") (pintype "passive"))
    )
    (net (code "58") (name "unconnected-(D5A-PG1-Pad9)") (class "Default")
      (node (ref "D5") (pin "9") (pinfunction "PG1_9") (pintype "passive"))
    )
    (net (code "59") (name "unconnected-(D5B-PG2-Pad12)") (class "Default")
      (node (ref "D5") (pin "12") (pinfunction "PG2_12") (pintype "passive"))
    )
  )
)
